# Tone_board.net
KiCad netlist of a schematic drawn in Altium Designer
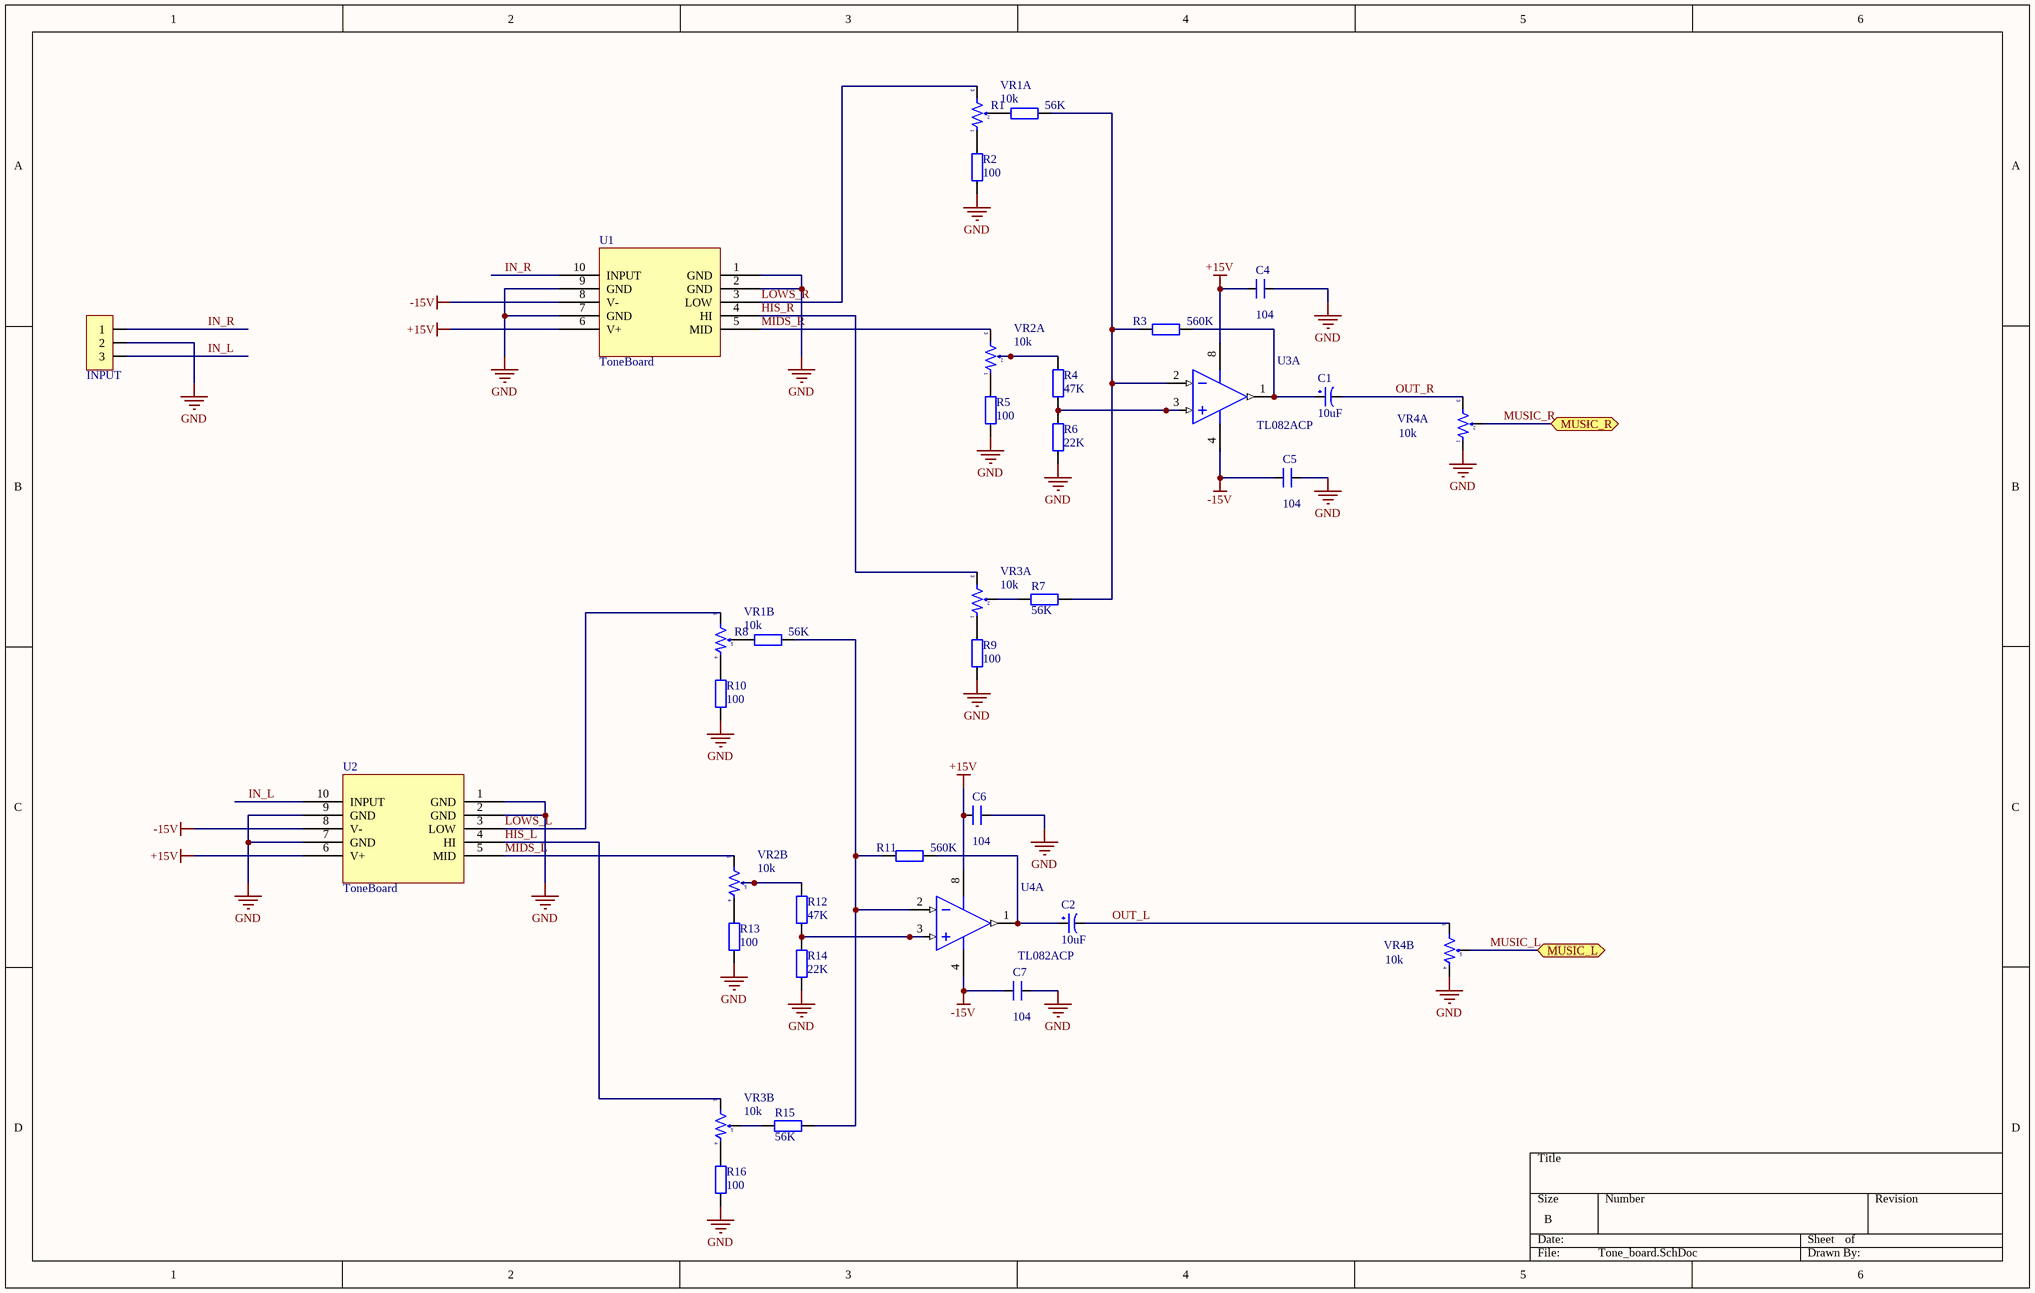
[diagram p0: Tone_board.SchDoc]

(export (version "E")
  (design (tool "Eeschema 10.0.6"))
  (components
    (comp (ref "C1")
      (value "10uF")
      (footprint "CAP5x12")
      (description "TU_HOA_4.7uF_100V_MH")
      (libsource (lib "MH_DA_THU_VIEN_16122016") (part "TU_HOA_4.7uF_100V_MH"))
    )
    (comp (ref "C2")
      (value "10uF")
      (footprint "CAP5x12")
      (description "TU_HOA_4.7uF_100V_MH")
      (libsource (lib "MH_DA_THU_VIEN_16122016") (part "TU_HOA_4.7uF_100V_MH"))
    )
    (comp (ref "C4")
      (value "104")
      (footprint "TU_GOM(104-->105pF)")
      (libsource (lib "MH_DA_THU_VIEN_16122016") (part "TU_MICA_ 104 100V(2A104J)_MH"))
    )
    (comp (ref "C5")
      (value "104")
      (footprint "TU_GOM(104-->105pF)")
      (libsource (lib "MH_DA_THU_VIEN_16122016") (part "TU_MICA_ 104 100V(2A104J)_MH"))
    )
    (comp (ref "C6")
      (value "104")
      (footprint "TU_GOM(104-->105pF)")
      (libsource (lib "MH_DA_THU_VIEN_16122016") (part "TU_MICA_ 104 100V(2A104J)_MH"))
    )
    (comp (ref "C7")
      (value "104")
      (footprint "TU_GOM(104-->105pF)")
      (libsource (lib "MH_DA_THU_VIEN_16122016") (part "TU_MICA_ 104 100V(2A104J)_MH"))
    )
    (comp (ref "INPUT")
      (value "Header 3_MH")
      (footprint "HEADER 3")
      (description "Header 3P XH2.54 thẳng")
      (libsource (lib "MH_DA_THU_VIEN_16122016") (part "Header 3_MH"))
    )
    (comp (ref "R1")
      (value "56K")
      (footprint "TRO_VACH_ 1/4W")
      (description "Resistor")
      (fields (field (name "PUBLISHER") "Altium Limited"))
      (libsource (lib "") (part "TRO_VACH_1/2W_MH_1"))
    )
    (comp (ref "R2")
      (value "100")
      (footprint "TRO_VACH_ 1/4W")
      (description "100 Ohms ±1% 0.25W, 1/4W Through Hole Resistor Axial Metal Film")
      (fields
        (field (name "MANUFACTURER PART NUMBER") "MFR-25FBF52-100R")
        (field (name "PUBLISHER") "Altium Limited")
      )
      (libsource (lib "MH_DA_THU_VIEN_16122016") (part "TRO_VACH_1/2W_MH"))
    )
    (comp (ref "R3")
      (value "560K")
      (footprint "TRO_VACH_ 1/4W")
      (description "Resistor")
      (fields (field (name "PUBLISHER") "Altium Limited"))
      (libsource (lib "") (part "TRO_VACH_1/2W_MH_1"))
    )
    (comp (ref "R4")
      (value "47K")
      (footprint "TRO_VACH_ 1/4W")
      (description "Resistor")
      (fields (field (name "PUBLISHER") "Altium Limited"))
      (libsource (lib "MH_DA_THU_VIEN_16122016") (part "TRO_VACH_1/2W_MH"))
    )
    (comp (ref "R5")
      (value "100")
      (footprint "TRO_VACH_ 1/4W")
      (description "Resistor")
      (fields (field (name "PUBLISHER") "Altium Limited"))
      (libsource (lib "MH_DA_THU_VIEN_16122016") (part "TRO_VACH_1/2W_MH"))
    )
    (comp (ref "R6")
      (value "22K")
      (footprint "TRO_VACH_ 1/4W")
      (description "Resistor")
      (fields (field (name "PUBLISHER") "Altium Limited"))
      (libsource (lib "MH_DA_THU_VIEN_16122016") (part "TRO_VACH_1/2W_MH"))
    )
    (comp (ref "R7")
      (value "56K")
      (footprint "TRO_VACH_ 1/4W")
      (description "Resistor")
      (fields (field (name "PUBLISHER") "Altium Limited"))
      (libsource (lib "") (part "TRO_VACH_1/2W_MH_1"))
    )
    (comp (ref "R8")
      (value "56K")
      (footprint "TRO_VACH_ 1/4W")
      (description "Resistor")
      (fields (field (name "PUBLISHER") "Altium Limited"))
      (libsource (lib "") (part "TRO_VACH_1/2W_MH_1"))
    )
    (comp (ref "R9")
      (value "100")
      (footprint "TRO_VACH_ 1/4W")
      (description "Resistor")
      (fields (field (name "PUBLISHER") "Altium Limited"))
      (libsource (lib "MH_DA_THU_VIEN_16122016") (part "TRO_VACH_1/2W_MH"))
    )
    (comp (ref "R10")
      (value "100")
      (footprint "TRO_VACH_ 1/4W")
      (description "Resistor")
      (fields (field (name "PUBLISHER") "Altium Limited"))
      (libsource (lib "MH_DA_THU_VIEN_16122016") (part "TRO_VACH_1/2W_MH"))
    )
    (comp (ref "R11")
      (value "560K")
      (footprint "TRO_VACH_ 1/4W")
      (description "Resistor")
      (fields (field (name "PUBLISHER") "Altium Limited"))
      (libsource (lib "") (part "TRO_VACH_1/2W_MH_1"))
    )
    (comp (ref "R12")
      (value "47K")
      (footprint "TRO_VACH_ 1/4W")
      (description "Resistor")
      (fields (field (name "PUBLISHER") "Altium Limited"))
      (libsource (lib "MH_DA_THU_VIEN_16122016") (part "TRO_VACH_1/2W_MH"))
    )
    (comp (ref "R13")
      (value "100")
      (footprint "TRO_VACH_ 1/4W")
      (description "Resistor")
      (fields (field (name "PUBLISHER") "Altium Limited"))
      (libsource (lib "MH_DA_THU_VIEN_16122016") (part "TRO_VACH_1/2W_MH"))
    )
    (comp (ref "R14")
      (value "22K")
      (footprint "TRO_VACH_ 1/4W")
      (description "Resistor")
      (fields (field (name "PUBLISHER") "Altium Limited"))
      (libsource (lib "MH_DA_THU_VIEN_16122016") (part "TRO_VACH_1/2W_MH"))
    )
    (comp (ref "R15")
      (value "56K")
      (footprint "TRO_VACH_ 1/4W")
      (description "Resistor")
      (fields (field (name "PUBLISHER") "Altium Limited"))
      (libsource (lib "") (part "TRO_VACH_1/2W_MH_1"))
    )
    (comp (ref "R16")
      (value "100")
      (footprint "TRO_VACH_ 1/4W")
      (description "Resistor")
      (fields (field (name "PUBLISHER") "Altium Limited"))
      (libsource (lib "MH_DA_THU_VIEN_16122016") (part "TRO_VACH_1/2W_MH"))
    )
    (comp (ref "U1")
      (value "ToneBoard")
      (footprint "ToneBoard")
      (libsource (lib "Schlib1") (part "ToneBoard"))
    )
    (comp (ref "U2")
      (value "ToneBoard")
      (footprint "ToneBoard")
      (libsource (lib "Schlib1") (part "ToneBoard"))
    )
    (comp (ref "U3")
      (value "TL082ACP")
      (footprint "DIP8")
      (description "JFET-Input Operational Amplifier")
      (fields (field (name "PUBLISHER") "Altium Limited"))
      (libsource (lib "Schlib1") (part "TL082ACP"))
    )
    (comp (ref "U4")
      (value "TL082ACP")
      (footprint "DIP8")
      (description "JFET-Input Operational Amplifier")
      (fields (field (name "PUBLISHER") "Altium Limited"))
      (libsource (lib "Schlib1") (part "TL082ACP"))
    )
    (comp (ref "VR1")
      (value "10k")
      (footprint "9011")
      (description "Triet Ap Doi 10k")
      (libsource (lib "Schlib1") (part "Triet Ap Doi 10k_MH"))
    )
    (comp (ref "VR2")
      (value "10k")
      (footprint "9011")
      (description "Triet Ap Doi 10k")
      (libsource (lib "Schlib1") (part "Triet Ap Doi 10k_MH"))
    )
    (comp (ref "VR3")
      (value "10k")
      (footprint "9011")
      (description "Triet Ap Doi 10k")
      (libsource (lib "Schlib1") (part "Triet Ap Doi 10k_MH"))
    )
    (comp (ref "VR4")
      (value "10k")
      (footprint "9011")
      (description "Triet Ap Doi 10k")
      (libsource (lib "Schlib1") (part "Triet Ap Doi 10k_MH"))
    )
  )
  (nets
    (net (code "1") (name "+15V") (class "Default")
      (node (ref "C4") (pin "1") (pinfunction "1_1") (pintype "passive"))
      (node (ref "C6") (pin "1") (pinfunction "1_1") (pintype "passive"))
      (node (ref "U1") (pin "6") (pinfunction "V+_6") (pintype "passive"))
      (node (ref "U2") (pin "6") (pinfunction "V+_6") (pintype "passive"))
      (node (ref "U3") (pin "8") (pinfunction "V+_8") (pintype "power_in"))
      (node (ref "U4") (pin "8") (pinfunction "V+_8") (pintype "power_in"))
    )
    (net (code "2") (name "-15V") (class "Default")
      (node (ref "C5") (pin "1") (pinfunction "1_1") (pintype "passive"))
      (node (ref "C7") (pin "1") (pinfunction "1_1") (pintype "passive"))
      (node (ref "U1") (pin "8") (pinfunction "V-_8") (pintype "passive"))
      (node (ref "U2") (pin "8") (pinfunction "V-_8") (pintype "passive"))
      (node (ref "U3") (pin "4") (pinfunction "V-_4") (pintype "power_in"))
      (node (ref "U4") (pin "4") (pinfunction "V-_4") (pintype "power_in"))
    )
    (net (code "3") (name "/HIS_L") (class "Default")
      (node (ref "U2") (pin "4") (pinfunction "HI_4") (pintype "passive"))
      (node (ref "VR3") (pin "6") (pinfunction "6_6") (pintype "passive"))
    )
    (net (code "4") (name "/HIS_R") (class "Default")
      (node (ref "U1") (pin "4") (pinfunction "HI_4") (pintype "passive"))
      (node (ref "VR3") (pin "3") (pinfunction "3_3") (pintype "passive"))
    )
    (net (code "5") (name "/IN_L") (class "Default")
      (node (ref "INPUT") (pin "3") (pinfunction "3_3") (pintype "passive"))
      (node (ref "U2") (pin "10") (pinfunction "INPUT_10") (pintype "passive"))
    )
    (net (code "6") (name "/IN_R") (class "Default")
      (node (ref "INPUT") (pin "1") (pinfunction "1_1") (pintype "passive"))
      (node (ref "U1") (pin "10") (pinfunction "INPUT_10") (pintype "passive"))
    )
    (net (code "7") (name "/LOWS_L") (class "Default")
      (node (ref "U2") (pin "3") (pinfunction "LOW_3") (pintype "passive"))
      (node (ref "VR1") (pin "6") (pinfunction "6_6") (pintype "passive"))
    )
    (net (code "8") (name "/LOWS_R") (class "Default")
      (node (ref "U1") (pin "3") (pinfunction "LOW_3") (pintype "passive"))
      (node (ref "VR1") (pin "3") (pinfunction "3_3") (pintype "passive"))
    )
    (net (code "9") (name "/MIDS_L") (class "Default")
      (node (ref "U2") (pin "5") (pinfunction "MID_5") (pintype "passive"))
      (node (ref "VR2") (pin "6") (pinfunction "6_6") (pintype "passive"))
    )
    (net (code "10") (name "/MIDS_R") (class "Default")
      (node (ref "U1") (pin "5") (pinfunction "MID_5") (pintype "passive"))
      (node (ref "VR2") (pin "3") (pinfunction "3_3") (pintype "passive"))
    )
    (net (code "11") (name "/MUSIC_L") (class "Default")
      (node (ref "VR4") (pin "5") (pinfunction "5_5") (pintype "passive"))
    )
    (net (code "12") (name "/MUSIC_R") (class "Default")
      (node (ref "VR4") (pin "2") (pinfunction "2_2") (pintype "passive"))
    )
    (net (code "13") (name "/OUT_L") (class "Default")
      (node (ref "C2") (pin "2") (pinfunction "2_2") (pintype "passive"))
      (node (ref "VR4") (pin "6") (pinfunction "6_6") (pintype "passive"))
    )
    (net (code "14") (name "/OUT_R") (class "Default")
      (node (ref "C1") (pin "2") (pinfunction "2_2") (pintype "passive"))
      (node (ref "VR4") (pin "3") (pinfunction "3_3") (pintype "passive"))
    )
    (net (code "15") (name "GND") (class "Default")
      (node (ref "C4") (pin "2") (pinfunction "2_2") (pintype "passive"))
      (node (ref "C5") (pin "2") (pinfunction "2_2") (pintype "passive"))
      (node (ref "C6") (pin "2") (pinfunction "2_2") (pintype "passive"))
      (node (ref "C7") (pin "2") (pinfunction "2_2") (pintype "passive"))
      (node (ref "INPUT") (pin "2") (pinfunction "2_2") (pintype "passive"))
      (node (ref "R10") (pin "1") (pinfunction "1_1") (pintype "passive"))
      (node (ref "R13") (pin "1") (pinfunction "1_1") (pintype "passive"))
      (node (ref "R14") (pin "1") (pinfunction "1_1") (pintype "passive"))
      (node (ref "R16") (pin "1") (pinfunction "1_1") (pintype "passive"))
      (node (ref "R2") (pin "1") (pinfunction "1_1") (pintype "passive"))
      (node (ref "R5") (pin "1") (pinfunction "1_1") (pintype "passive"))
      (node (ref "R6") (pin "1") (pinfunction "1_1") (pintype "passive"))
      (node (ref "R9") (pin "1") (pinfunction "1_1") (pintype "passive"))
      (node (ref "U1") (pin "1") (pinfunction "GND_1") (pintype "passive"))
      (node (ref "U1") (pin "2") (pinfunction "GND_2") (pintype "passive"))
      (node (ref "U1") (pin "7") (pinfunction "GND_7") (pintype "passive"))
      (node (ref "U1") (pin "9") (pinfunction "GND_9") (pintype "passive"))
      (node (ref "U2") (pin "1") (pinfunction "GND_1") (pintype "passive"))
      (node (ref "U2") (pin "2") (pinfunction "GND_2") (pintype "passive"))
      (node (ref "U2") (pin "7") (pinfunction "GND_7") (pintype "passive"))
      (node (ref "U2") (pin "9") (pinfunction "GND_9") (pintype "passive"))
      (node (ref "VR4") (pin "1") (pinfunction "1_1") (pintype "passive"))
      (node (ref "VR4") (pin "4") (pinfunction "4_4") (pintype "passive"))
    )
    (net (code "16") (name "Net-(R1-Pad2)") (class "Default")
      (node (ref "R1") (pin "2") (pinfunction "2_2") (pintype "passive"))
      (node (ref "VR1") (pin "2") (pinfunction "2_2") (pintype "passive"))
    )
    (net (code "17") (name "Net-(R2-Pad2)") (class "Default")
      (node (ref "R2") (pin "2") (pinfunction "2_2") (pintype "passive"))
      (node (ref "VR1") (pin "1") (pinfunction "1_1") (pintype "passive"))
    )
    (net (code "18") (name "Net-(R4-Pad2)") (class "Default")
      (node (ref "R4") (pin "2") (pinfunction "2_2") (pintype "passive"))
      (node (ref "VR2") (pin "2") (pinfunction "2_2") (pintype "passive"))
    )
    (net (code "19") (name "Net-(R5-Pad2)") (class "Default")
      (node (ref "R5") (pin "2") (pinfunction "2_2") (pintype "passive"))
      (node (ref "VR2") (pin "1") (pinfunction "1_1") (pintype "passive"))
    )
    (net (code "20") (name "Net-(R7-Pad2)") (class "Default")
      (node (ref "R7") (pin "2") (pinfunction "2_2") (pintype "passive"))
      (node (ref "VR3") (pin "2") (pinfunction "2_2") (pintype "passive"))
    )
    (net (code "21") (name "Net-(R8-Pad2)") (class "Default")
      (node (ref "R8") (pin "2") (pinfunction "2_2") (pintype "passive"))
      (node (ref "VR1") (pin "5") (pinfunction "5_5") (pintype "passive"))
    )
    (net (code "22") (name "Net-(R9-Pad2)") (class "Default")
      (node (ref "R9") (pin "2") (pinfunction "2_2") (pintype "passive"))
      (node (ref "VR3") (pin "1") (pinfunction "1_1") (pintype "passive"))
    )
    (net (code "23") (name "Net-(R10-Pad2)") (class "Default")
      (node (ref "R10") (pin "2") (pinfunction "2_2") (pintype "passive"))
      (node (ref "VR1") (pin "4") (pinfunction "4_4") (pintype "passive"))
    )
    (net (code "24") (name "Net-(R12-Pad2)") (class "Default")
      (node (ref "R12") (pin "2") (pinfunction "2_2") (pintype "passive"))
      (node (ref "VR2") (pin "5") (pinfunction "5_5") (pintype "passive"))
    )
    (net (code "25") (name "Net-(R13-Pad2)") (class "Default")
      (node (ref "R13") (pin "2") (pinfunction "2_2") (pintype "passive"))
      (node (ref "VR2") (pin "4") (pinfunction "4_4") (pintype "passive"))
    )
    (net (code "26") (name "Net-(R15-Pad2)") (class "Default")
      (node (ref "R15") (pin "2") (pinfunction "2_2") (pintype "passive"))
      (node (ref "VR3") (pin "5") (pinfunction "5_5") (pintype "passive"))
    )
    (net (code "27") (name "Net-(R16-Pad2)") (class "Default")
      (node (ref "R16") (pin "2") (pinfunction "2_2") (pintype "passive"))
      (node (ref "VR3") (pin "4") (pinfunction "4_4") (pintype "passive"))
    )
    (net (code "28") (name "Net-(U3A-IN+)") (class "Default")
      (node (ref "R4") (pin "1") (pinfunction "1_1") (pintype "passive"))
      (node (ref "R6") (pin "2") (pinfunction "2_2") (pintype "passive"))
      (node (ref "U3") (pin "3") (pinfunction "IN+_3") (pintype "input"))
    )
    (net (code "29") (name "Net-(U3A-IN-)") (class "Default")
      (node (ref "R1") (pin "1") (pinfunction "1_1") (pintype "passive"))
      (node (ref "R3") (pin "2") (pinfunction "2_2") (pintype "passive"))
      (node (ref "R7") (pin "1") (pinfunction "1_1") (pintype "passive"))
      (node (ref "U3") (pin "2") (pinfunction "IN-_2") (pintype "input"))
    )
    (net (code "30") (name "Net-(U3A-OUT)") (class "Default")
      (node (ref "C1") (pin "1") (pinfunction "1_1") (pintype "passive"))
      (node (ref "R3") (pin "1") (pinfunction "1_1") (pintype "passive"))
      (node (ref "U3") (pin "1") (pinfunction "OUT_1") (pintype "output"))
    )
    (net (code "31") (name "Net-(U4A-IN+)") (class "Default")
      (node (ref "R12") (pin "1") (pinfunction "1_1") (pintype "passive"))
      (node (ref "R14") (pin "2") (pinfunction "2_2") (pintype "passive"))
      (node (ref "U4") (pin "3") (pinfunction "IN+_3") (pintype "input"))
    )
    (net (code "32") (name "Net-(U4A-IN-)") (class "Default")
      (node (ref "R11") (pin "2") (pinfunction "2_2") (pintype "passive"))
      (node (ref "R15") (pin "1") (pinfunction "1_1") (pintype "passive"))
      (node (ref "R8") (pin "1") (pinfunction "1_1") (pintype "passive"))
      (node (ref "U4") (pin "2") (pinfunction "IN-_2") (pintype "input"))
    )
    (net (code "33") (name "Net-(U4A-OUT)") (class "Default")
      (node (ref "C2") (pin "1") (pinfunction "1_1") (pintype "passive"))
      (node (ref "R11") (pin "1") (pinfunction "1_1") (pintype "passive"))
      (node (ref "U4") (pin "1") (pinfunction "OUT_1") (pintype "output"))
    )
  )
)
